# Tag.net
KiCad netlist of a schematic drawn in EasyEDA Pro
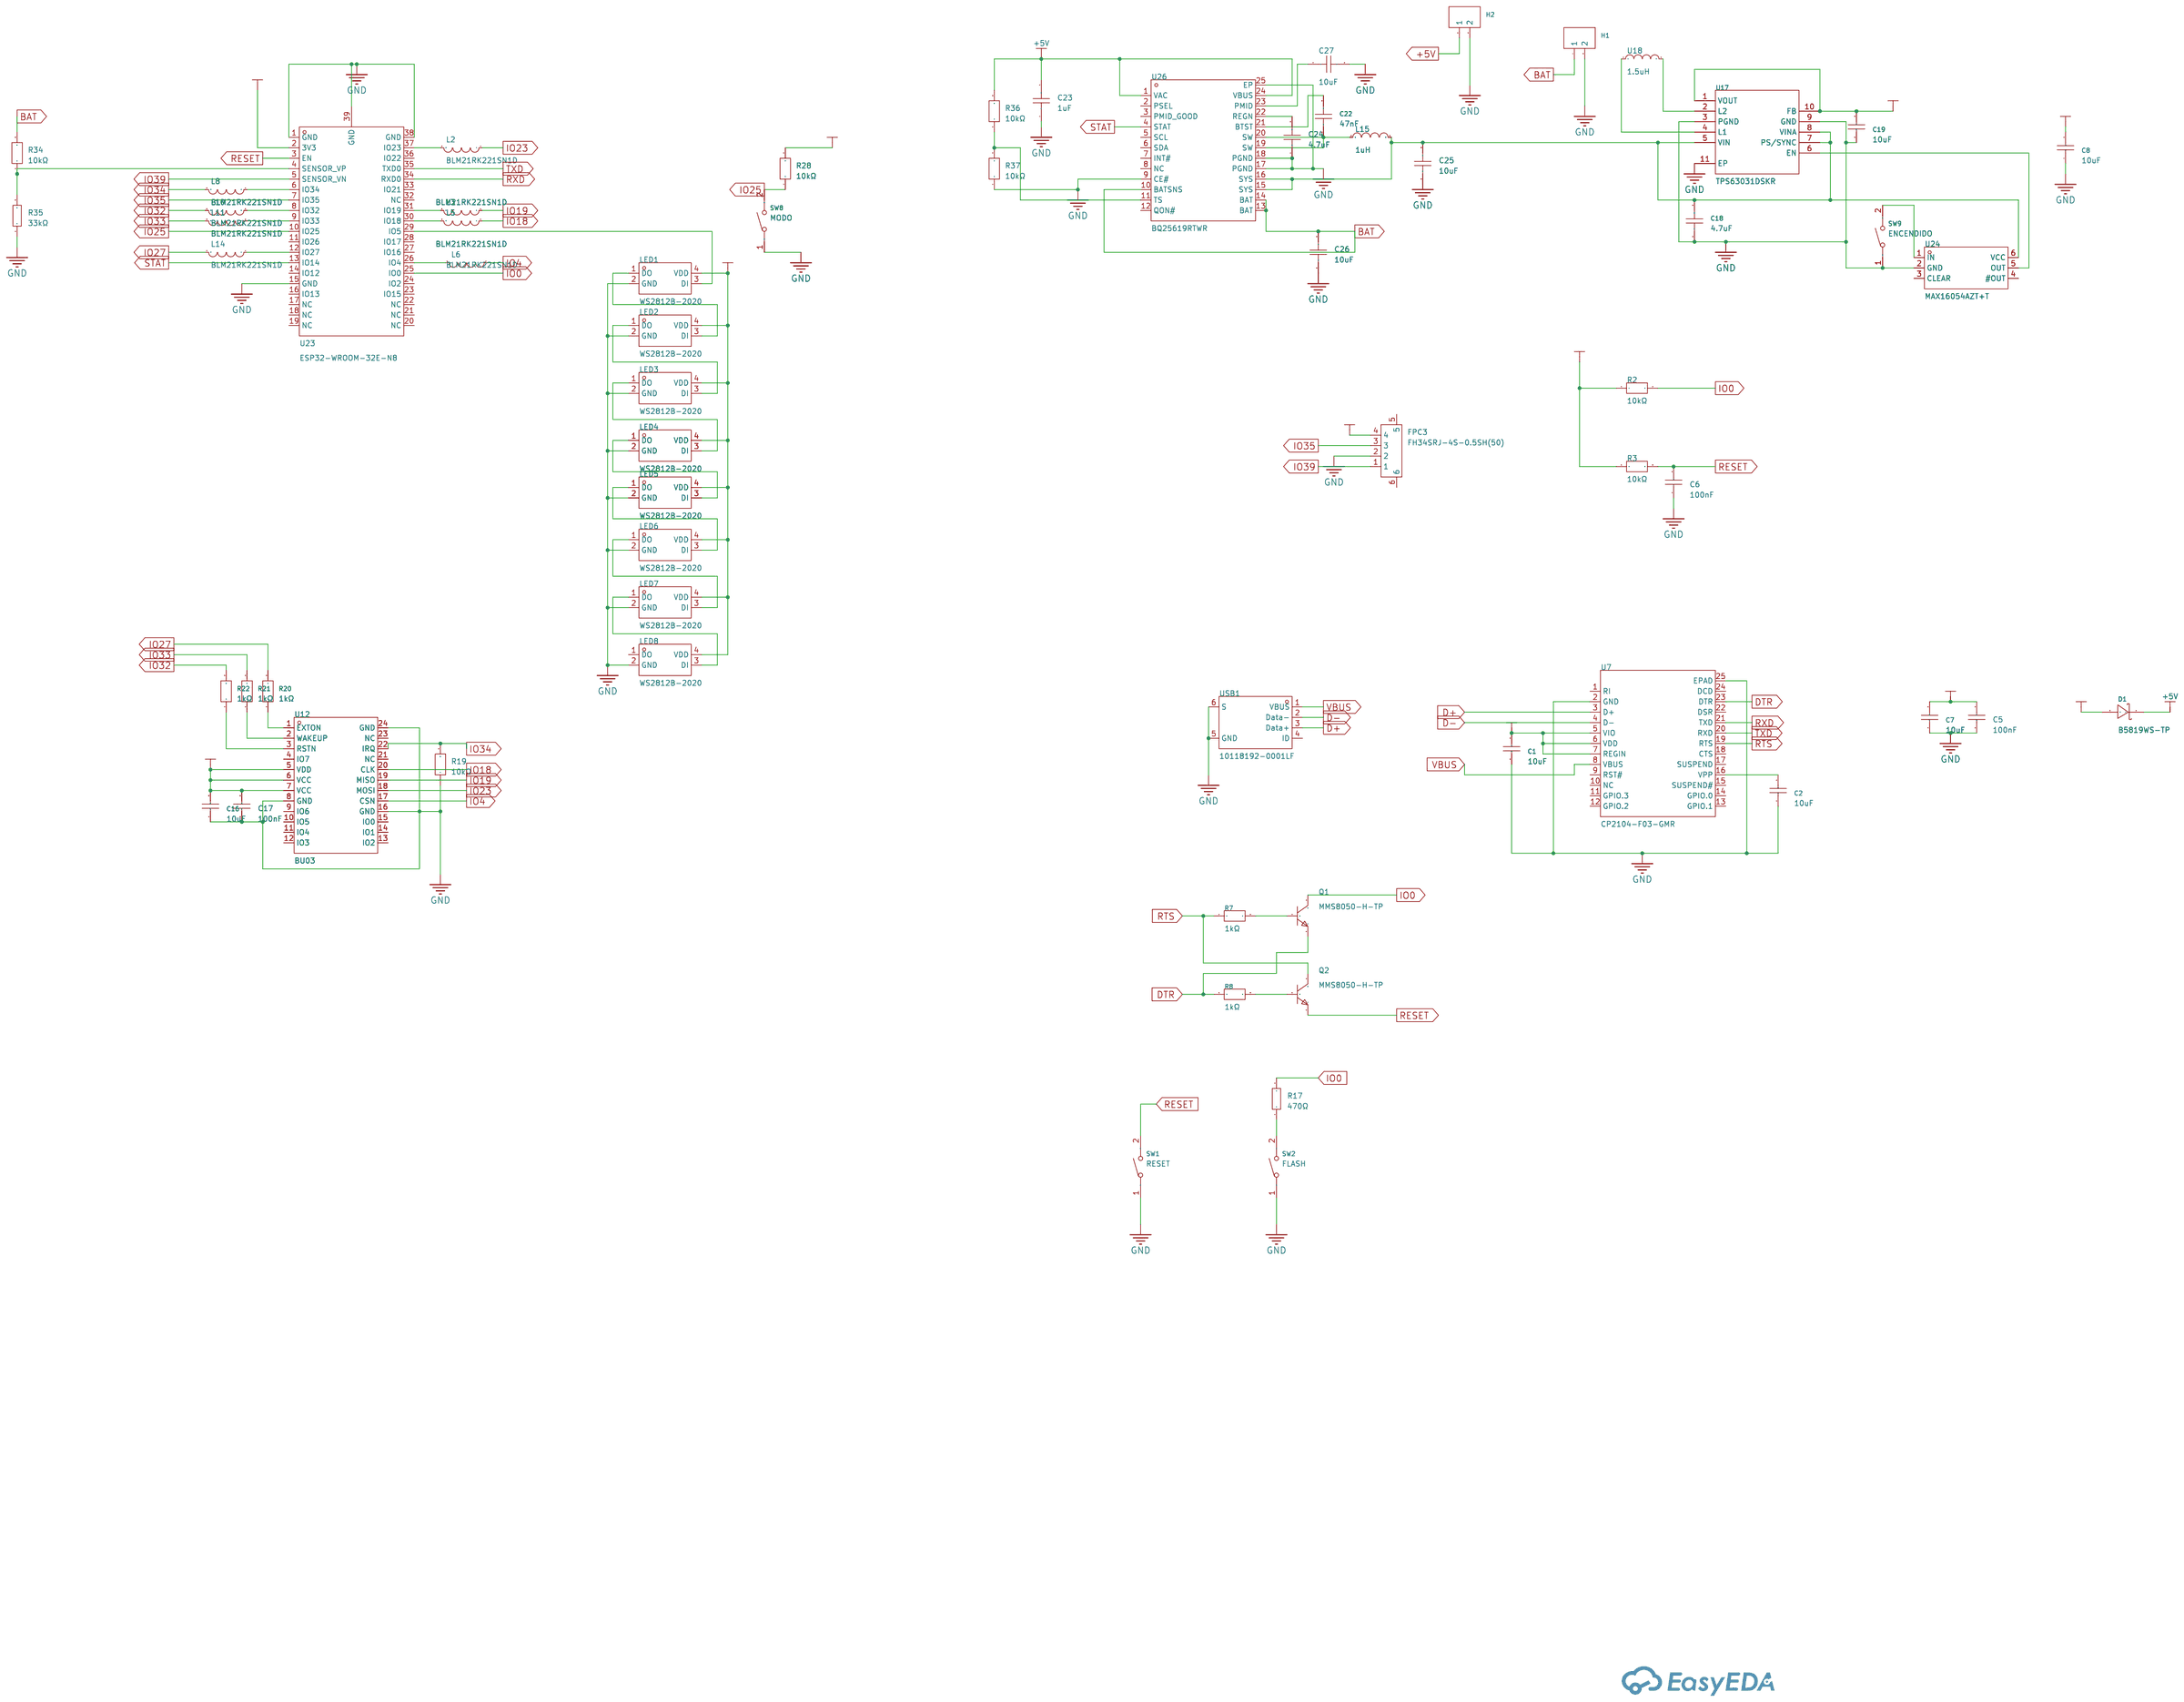
[diagram p0: schematic sheet]

(export (version "E")
  (design (tool "Eeschema 10.0.6"))
  (components
    (comp (ref "C1")
      (value "10uF")
      (footprint "easyedapro:C0805")
      (fields
        (field (name "Manufacturer Part") "CL21A106KPFNNNE")
        (field (name "Manufacturer") "SAMSUNG(三星)")
      )
      (libsource (lib "easyedapro") (part "CL21A106KPFNNNE"))
    )
    (comp (ref "C2")
      (value "10uF")
      (footprint "easyedapro:C0805")
      (fields
        (field (name "Manufacturer Part") "CL21A106KPFNNNE")
        (field (name "Manufacturer") "SAMSUNG(三星)")
      )
      (libsource (lib "easyedapro") (part "CL21A106KPFNNNE"))
    )
    (comp (ref "C5")
      (value "100nF")
      (footprint "easyedapro:C0805")
      (description "Capacitance:100nF Tolerance:±5% Tolerance:±5% Voltage Rating:50V Temperature Coefficient:X7R")
      (fields (field (name "Manufacturer Part") "0805B104J500NT") (field (name "Manufacturer") "FH(风华)"))
      (libsource (lib "easyedapro") (part "0805B104J500NT"))
    )
    (comp (ref "C6")
      (value "100nF")
      (footprint "easyedapro:C0805")
      (description "Capacitance:100nF Tolerance:±5% Tolerance:±5% Voltage Rating:50V Temperature Coefficient:X7R")
      (fields (field (name "Manufacturer Part") "0805B104J500NT") (field (name "Manufacturer") "FH(风华)"))
      (libsource (lib "easyedapro") (part "0805B104J500NT"))
    )
    (comp (ref "C7")
      (value "10uF")
      (footprint "easyedapro:C0805")
      (fields
        (field (name "Manufacturer Part") "CL21A106KPFNNNE")
        (field (name "Manufacturer") "SAMSUNG(三星)")
      )
      (libsource (lib "easyedapro") (part "CL21A106KPFNNNE"))
    )
    (comp (ref "C8")
      (value "10uF")
      (footprint "easyedapro:C0805")
      (fields
        (field (name "Manufacturer Part") "CL21A106KPFNNNE")
        (field (name "Manufacturer") "SAMSUNG(三星)")
      )
      (libsource (lib "easyedapro") (part "CL21A106KPFNNNE"))
    )
    (comp (ref "C16")
      (value "10uF")
      (footprint "easyedapro:C0805")
      (fields
        (field (name "Manufacturer Part") "CL21A106KPFNNNE")
        (field (name "Manufacturer") "SAMSUNG(三星)")
      )
      (libsource (lib "easyedapro") (part "CL21A106KPFNNNE"))
    )
    (comp (ref "C17")
      (value "100nF")
      (footprint "easyedapro:C0805")
      (description "Capacitance:100nF Tolerance:±5% Tolerance:±5% Voltage Rating:50V Temperature Coefficient:X7R")
      (fields (field (name "Manufacturer Part") "0805B104J500NT") (field (name "Manufacturer") "FH(风华)"))
      (libsource (lib "easyedapro") (part "0805B104J500NT"))
    )
    (comp (ref "C18")
      (value "4.7uF")
      (footprint "easyedapro:C0805")
      (fields
        (field (name "Manufacturer Part") "CC0805KKX7R5BB475")
        (field (name "Manufacturer") "YAGEO(国巨)")
      )
      (libsource (lib "easyedapro") (part "CC0805KKX7R5BB475"))
    )
    (comp (ref "C19")
      (value "10uF")
      (footprint "easyedapro:C0805")
      (fields
        (field (name "Manufacturer Part") "GCM21BR70J106KE22L")
        (field (name "Manufacturer") "muRata(村田)")
      )
      (libsource (lib "easyedapro") (part "GCM21BR70J106KE22L"))
    )
    (comp (ref "C22")
      (value "47nF")
      (footprint "easyedapro:C0805")
      (description "Capacitance:47nF Tolerance:±5% Tolerance:±5% Voltage Rating:50V Temperature Coefficient:X7R")
      (fields
        (field (name "Manufacturer Part") "CC0805JRX7R9BB473")
        (field (name "Manufacturer") "YAGEO(国巨)")
      )
      (libsource (lib "easyedapro") (part "CC0805JRX7R9BB473"))
    )
    (comp (ref "C23")
      (value "1uF")
      (footprint "easyedapro:C0805")
      (fields
        (field (name "Manufacturer Part") "CC0805JKX7R9BB105")
        (field (name "Manufacturer") "YAGEO(国巨)")
      )
      (libsource (lib "easyedapro") (part "CC0805JKX7R9BB105"))
    )
    (comp (ref "C24")
      (value "4.7uF")
      (footprint "easyedapro:C0805")
      (description "Capacitance:4.7uF Tolerance:±5% Tolerance:±5% Voltage Rating:6.3V Temperature Coefficient:X7R")
      (fields
        (field (name "Manufacturer Part") "C0805C475J9RACAUTO")
        (field (name "Manufacturer") "KEMET(基美)")
      )
      (libsource (lib "easyedapro") (part "C0805C475J9RACAUTO"))
    )
    (comp (ref "C25")
      (value "10uF")
      (footprint "easyedapro:C1206")
      (fields
        (field (name "Manufacturer Part") "C1206C106J3RACAUTO")
        (field (name "Manufacturer") "KEMET(基美)")
      )
      (libsource (lib "easyedapro") (part "C1206C106J3RACAUTO"))
    )
    (comp (ref "C26")
      (value "10uF")
      (footprint "easyedapro:C1206")
      (fields
        (field (name "Manufacturer Part") "C1206C106J3RACAUTO")
        (field (name "Manufacturer") "KEMET(基美)")
      )
      (libsource (lib "easyedapro") (part "C1206C106J3RACAUTO"))
    )
    (comp (ref "C27")
      (value "10uF")
      (footprint "easyedapro:C1206")
      (fields
        (field (name "Manufacturer Part") "C1206C106J3RACAUTO")
        (field (name "Manufacturer") "KEMET(基美)")
      )
      (libsource (lib "easyedapro") (part "C1206C106J3RACAUTO"))
    )
    (comp (ref "D1")
      (value "B5819WS-TP")
      (footprint "easyedapro:SOD-323_L1.8-W1.3-LS2.5-RD")
      (fields (field (name "Manufacturer") "MCC(美微科)"))
      (libsource (lib "easyedapro") (part "B5819WS-TP"))
    )
    (comp (ref "FPC3")
      (value "FH34SRJ-4S-0.5SH(50)")
      (footprint "easyedapro:FPC-SMD_FH34SRJ-4S-0.5SH-50")
      (fields (field (name "Manufacturer") "HRS(广濑)"))
      (libsource (lib "easyedapro") (part "FH34SRJ-4S-0.5SH(50)"))
    )
    (comp (ref "H1")
      (value "~")
      (footprint "easyedapro:HDR-TH_2P-P2.54-V-F")
      (libsource (lib "easyedapro") (part "Header-Female-2.54_1x2"))
    )
    (comp (ref "H2")
      (value "~")
      (footprint "easyedapro:HDR-TH_2P-P2.54-V-F")
      (libsource (lib "easyedapro") (part "Header-Female-2.54_1x2"))
    )
    (comp (ref "L2")
      (value "BLM21RK221SN1D")
      (footprint "easyedapro:L0805")
      (fields (field (name "Manufacturer") "muRata(村田)"))
      (libsource (lib "easyedapro") (part "BLM21RK221SN1D"))
    )
    (comp (ref "L3")
      (value "BLM21RK221SN1D")
      (footprint "easyedapro:L0805")
      (fields (field (name "Manufacturer") "muRata(村田)"))
      (libsource (lib "easyedapro") (part "BLM21RK221SN1D"))
    )
    (comp (ref "L5")
      (value "BLM21RK221SN1D")
      (footprint "easyedapro:L0805")
      (fields (field (name "Manufacturer") "muRata(村田)"))
      (libsource (lib "easyedapro") (part "BLM21RK221SN1D"))
    )
    (comp (ref "L6")
      (value "BLM21RK221SN1D")
      (footprint "easyedapro:L0805")
      (fields (field (name "Manufacturer") "muRata(村田)"))
      (libsource (lib "easyedapro") (part "BLM21RK221SN1D"))
    )
    (comp (ref "L8")
      (value "BLM21RK221SN1D")
      (footprint "easyedapro:L0805")
      (fields (field (name "Manufacturer") "muRata(村田)"))
      (libsource (lib "easyedapro") (part "BLM21RK221SN1D"))
    )
    (comp (ref "L10")
      (value "BLM21RK221SN1D")
      (footprint "easyedapro:L0805")
      (fields (field (name "Manufacturer") "muRata(村田)"))
      (libsource (lib "easyedapro") (part "BLM21RK221SN1D"))
    )
    (comp (ref "L11")
      (value "BLM21RK221SN1D")
      (footprint "easyedapro:L0805")
      (fields (field (name "Manufacturer") "muRata(村田)"))
      (libsource (lib "easyedapro") (part "BLM21RK221SN1D"))
    )
    (comp (ref "L14")
      (value "BLM21RK221SN1D")
      (footprint "easyedapro:L0805")
      (fields (field (name "Manufacturer") "muRata(村田)"))
      (libsource (lib "easyedapro") (part "BLM21RK221SN1D"))
    )
    (comp (ref "L15")
      (value "1uH")
      (footprint "easyedapro:IND-SMD_L5.4-W5.1")
      (description "Inductance:1uH Tolerance:±20% Tolerance:±20% Current Rating:5A DC Resistance(DCR):15mΩ")
      (fields
        (field (name "Manufacturer Part") "SLO0520H1R0MTT")
        (field (name "Manufacturer") "Sunltech(顺磁)")
      )
      (libsource (lib "easyedapro") (part "SLO0520H1R0MTT"))
    )
    (comp (ref "LED1")
      (value "WS2812B-2020")
      (footprint "easyedapro:LED-SMD_4P-L2.0-W2.0-TL_WS2812B-2020")
      (fields (field (name "Manufacturer") "worldsemi"))
      (libsource (lib "easyedapro") (part "WS2812B-2020"))
    )
    (comp (ref "LED2")
      (value "WS2812B-2020")
      (footprint "easyedapro:LED-SMD_4P-L2.0-W2.0-TL_WS2812B-2020")
      (fields (field (name "Manufacturer") "worldsemi"))
      (libsource (lib "easyedapro") (part "WS2812B-2020"))
    )
    (comp (ref "LED3")
      (value "WS2812B-2020")
      (footprint "easyedapro:LED-SMD_4P-L2.0-W2.0-TL_WS2812B-2020")
      (fields (field (name "Manufacturer") "worldsemi"))
      (libsource (lib "easyedapro") (part "WS2812B-2020"))
    )
    (comp (ref "LED4")
      (value "WS2812B-2020")
      (footprint "easyedapro:LED-SMD_4P-L2.0-W2.0-TL_WS2812B-2020")
      (fields (field (name "Manufacturer") "worldsemi"))
      (libsource (lib "easyedapro") (part "WS2812B-2020"))
    )
    (comp (ref "LED5")
      (value "WS2812B-2020")
      (footprint "easyedapro:LED-SMD_4P-L2.0-W2.0-TL_WS2812B-2020")
      (fields (field (name "Manufacturer") "worldsemi"))
      (libsource (lib "easyedapro") (part "WS2812B-2020"))
    )
    (comp (ref "LED6")
      (value "WS2812B-2020")
      (footprint "easyedapro:LED-SMD_4P-L2.0-W2.0-TL_WS2812B-2020")
      (fields (field (name "Manufacturer") "worldsemi"))
      (libsource (lib "easyedapro") (part "WS2812B-2020"))
    )
    (comp (ref "LED7")
      (value "WS2812B-2020")
      (footprint "easyedapro:LED-SMD_4P-L2.0-W2.0-TL_WS2812B-2020")
      (fields (field (name "Manufacturer") "worldsemi"))
      (libsource (lib "easyedapro") (part "WS2812B-2020"))
    )
    (comp (ref "LED8")
      (value "WS2812B-2020")
      (footprint "easyedapro:LED-SMD_4P-L2.0-W2.0-TL_WS2812B-2020")
      (fields (field (name "Manufacturer") "worldsemi"))
      (libsource (lib "easyedapro") (part "WS2812B-2020"))
    )
    (comp (ref "Q1")
      (value "MMS8050-H-TP")
      (footprint "easyedapro:SOT-23-3_L2.9-W1.3-P1.90-LS2.4-BR")
      (fields (field (name "Manufacturer") "MCC(美微科)"))
      (libsource (lib "easyedapro") (part "MMS8050-H-TP"))
    )
    (comp (ref "Q2")
      (value "MMS8050-H-TP")
      (footprint "easyedapro:SOT-23-3_L2.9-W1.3-P1.90-LS2.4-BR")
      (fields (field (name "Manufacturer") "MCC(美微科)"))
      (libsource (lib "easyedapro") (part "MMS8050-H-TP"))
    )
    (comp (ref "R2")
      (value "10kΩ")
      (footprint "easyedapro:R0805")
      (fields (field (name "Manufacturer Part") "ERJP06F1002V") (field (name "Manufacturer") "PANASONIC(松下)"))
      (libsource (lib "easyedapro") (part "ERJP06F1002V"))
    )
    (comp (ref "R3")
      (value "10kΩ")
      (footprint "easyedapro:R0805")
      (fields (field (name "Manufacturer Part") "ERJP06F1002V") (field (name "Manufacturer") "PANASONIC(松下)"))
      (libsource (lib "easyedapro") (part "ERJP06F1002V"))
    )
    (comp (ref "R7")
      (value "1kΩ")
      (footprint "easyedapro:R0805")
      (fields (field (name "Manufacturer Part") "ERJP06F1001V") (field (name "Manufacturer") "PANASONIC(松下)"))
      (libsource (lib "easyedapro") (part "ERJP06F1001V"))
    )
    (comp (ref "R8")
      (value "1kΩ")
      (footprint "easyedapro:R0805")
      (fields (field (name "Manufacturer Part") "ERJP06F1001V") (field (name "Manufacturer") "PANASONIC(松下)"))
      (libsource (lib "easyedapro") (part "ERJP06F1001V"))
    )
    (comp (ref "R17")
      (value "470Ω")
      (footprint "easyedapro:R0805")
      (fields (field (name "Manufacturer Part") "RC0805FR-07470RL") (field (name "Manufacturer") "YAGEO(国巨)"))
      (libsource (lib "easyedapro") (part "RC0805FR-07470RL"))
    )
    (comp (ref "R19")
      (value "10kΩ")
      (footprint "easyedapro:R0805")
      (fields (field (name "Manufacturer Part") "ERJP06F1002V") (field (name "Manufacturer") "PANASONIC(松下)"))
      (libsource (lib "easyedapro") (part "ERJP06F1002V"))
    )
    (comp (ref "R20")
      (value "1kΩ")
      (footprint "easyedapro:R0805")
      (fields (field (name "Manufacturer Part") "ERJP06F1001V") (field (name "Manufacturer") "PANASONIC(松下)"))
      (libsource (lib "easyedapro") (part "ERJP06F1001V"))
    )
    (comp (ref "R21")
      (value "1kΩ")
      (footprint "easyedapro:R0805")
      (fields (field (name "Manufacturer Part") "ERJP06F1001V") (field (name "Manufacturer") "PANASONIC(松下)"))
      (libsource (lib "easyedapro") (part "ERJP06F1001V"))
    )
    (comp (ref "R22")
      (value "1kΩ")
      (footprint "easyedapro:R0805")
      (fields (field (name "Manufacturer Part") "ERJP06F1001V") (field (name "Manufacturer") "PANASONIC(松下)"))
      (libsource (lib "easyedapro") (part "ERJP06F1001V"))
    )
    (comp (ref "R28")
      (value "10kΩ")
      (footprint "easyedapro:R0805")
      (fields (field (name "Manufacturer Part") "ERJP06F1002V") (field (name "Manufacturer") "PANASONIC(松下)"))
      (libsource (lib "easyedapro") (part "ERJP06F1002V"))
    )
    (comp (ref "R34")
      (value "10kΩ")
      (footprint "easyedapro:R0805")
      (fields (field (name "Manufacturer Part") "ERJP06F1002V") (field (name "Manufacturer") "PANASONIC(松下)"))
      (libsource (lib "easyedapro") (part "ERJP06F1002V"))
    )
    (comp (ref "R35")
      (value "33kΩ")
      (footprint "easyedapro:R0805")
      (fields (field (name "Manufacturer Part") "RC0805FR-0733KL") (field (name "Manufacturer") "YAGEO(国巨)"))
      (libsource (lib "easyedapro") (part "RC0805FR-0733KL"))
    )
    (comp (ref "R36")
      (value "10kΩ")
      (footprint "easyedapro:R0805")
      (fields (field (name "Manufacturer Part") "ERJP06F1002V") (field (name "Manufacturer") "PANASONIC(松下)"))
      (libsource (lib "easyedapro") (part "ERJP06F1002V"))
    )
    (comp (ref "R37")
      (value "10kΩ")
      (footprint "easyedapro:R0805")
      (fields (field (name "Manufacturer Part") "ERJP06F1002V") (field (name "Manufacturer") "PANASONIC(松下)"))
      (libsource (lib "easyedapro") (part "ERJP06F1002V"))
    )
    (comp (ref "SW1")
      (value "RESET")
      (footprint "easyedapro:SW-SMD_L3.9-W3.0-P4.45")
      (fields (field (name "Manufacturer Part") "TS-1088-AR02016") (field (name "Manufacturer") "XUNPU(讯普)"))
      (libsource (lib "easyedapro") (part "TS-1088-AR02016"))
    )
    (comp (ref "SW2")
      (value "FLASH")
      (footprint "easyedapro:SW-SMD_L3.9-W3.0-P4.45")
      (fields (field (name "Manufacturer Part") "TS-1088-AR02016") (field (name "Manufacturer") "XUNPU(讯普)"))
      (libsource (lib "easyedapro") (part "TS-1088-AR02016"))
    )
    (comp (ref "SW8")
      (value "MODO")
      (footprint "easyedapro:SW-SMD_L3.9-W3.0-P4.45")
      (fields (field (name "Manufacturer Part") "TS-1088-AR02016") (field (name "Manufacturer") "XUNPU(讯普)"))
      (libsource (lib "easyedapro") (part "TS-1088-AR02016"))
    )
    (comp (ref "SW9")
      (value "ENCENDIDO")
      (footprint "easyedapro:SW-SMD_L3.9-W3.0-P4.45")
      (fields (field (name "Manufacturer Part") "TS-1088-AR02016") (field (name "Manufacturer") "XUNPU(讯普)"))
      (libsource (lib "easyedapro") (part "TS-1088-AR02016"))
    )
    (comp (ref "U7")
      (value "CP2104-F03-GMR")
      (footprint "easyedapro:QFN-24_L4.0-W4.0-P0.50-BL-EP2.7")
      (fields (field (name "Manufacturer") "SKYWORKS/SILICON LABS(芯科)"))
      (libsource (lib "easyedapro") (part "CP2104-F03-GM"))
    )
    (comp (ref "U12")
      (value "BU03")
      (footprint "easyedapro:WIRELM-SMD_BU03")
      (fields (field (name "Manufacturer") "Ai-Thinker(安信可)"))
      (libsource (lib "easyedapro") (part "BU03"))
    )
    (comp (ref "U17")
      (value "TPS63031DSKR")
      (footprint "easyedapro:SON-10_L2.5-W2.5-P0.50-TL-EP")
      (fields (field (name "Manufacturer") "TI(德州仪器)"))
      (libsource (lib "easyedapro") (part "TPS63031DSKR"))
    )
    (comp (ref "U18")
      (value "1.5uH")
      (footprint "easyedapro:IND-SMD_L2.5-W2.0_MHCHL2520")
      (fields (field (name "Manufacturer Part") "SPM2512-1R5M") (field (name "Manufacturer") "KOHERelec(科或)"))
      (libsource (lib "easyedapro") (part "SPM2512-1R5M"))
    )
    (comp (ref "U23")
      (value "ESP32-WROOM-32E-N8")
      (footprint "easyedapro:WIFI-SMD_ESP32-WROOM-32E")
      (fields (field (name "Manufacturer") "ESPRESSIF(乐鑫)"))
      (libsource (lib "easyedapro") (part "ESP32-WROOM-32E(8MB)"))
    )
    (comp (ref "U24")
      (value "MAX16054AZT+T")
      (footprint "easyedapro:TSOT-23-6_L2.9-W1.6-P0.95-LS2.8-TL")
      (fields (field (name "Manufacturer") "ADI(亚德诺)"))
      (libsource (lib "easyedapro") (part "MAX16054AZT+T"))
    )
    (comp (ref "U26")
      (value "BQ25619RTWR")
      (footprint "easyedapro:WQFN-24_L4.0-W4.0-P0.50-TL-EP2.7")
      (fields (field (name "Manufacturer") "TI(德州仪器)"))
      (libsource (lib "easyedapro") (part "BQ25619RTWR"))
    )
    (comp (ref "USB1")
      (value "10118192-0001LF")
      (footprint "easyedapro:MICRO-USB-SMD_10118192-0001LF_1")
      (fields (field (name "Manufacturer") "Amphenol"))
      (libsource (lib "easyedapro") (part "10118192-0001LF"))
    )
  )
  (nets
    (net (code "1") (name "+3V3") (class "Default")
      (node (ref "C1") (pin "2") (pinfunction "2_2") (pintype "input"))
      (node (ref "C16") (pin "2") (pinfunction "2_2") (pintype "input"))
      (node (ref "C17") (pin "2") (pinfunction "2_2") (pintype "input"))
      (node (ref "C19") (pin "2") (pinfunction "2_2") (pintype "input"))
      (node (ref "C8") (pin "2") (pinfunction "2_2") (pintype "input"))
      (node (ref "FPC3") (pin "4") (pinfunction "4_4") (pintype "unspecified"))
      (node (ref "LED1") (pin "4") (pinfunction "VDD_4") (pintype "unspecified"))
      (node (ref "LED2") (pin "4") (pinfunction "VDD_4") (pintype "unspecified"))
      (node (ref "LED3") (pin "4") (pinfunction "VDD_4") (pintype "unspecified"))
      (node (ref "LED4") (pin "4") (pinfunction "VDD_4") (pintype "unspecified"))
      (node (ref "LED5") (pin "4") (pinfunction "VDD_4") (pintype "unspecified"))
      (node (ref "LED6") (pin "4") (pinfunction "VDD_4") (pintype "unspecified"))
      (node (ref "LED7") (pin "4") (pinfunction "VDD_4") (pintype "unspecified"))
      (node (ref "LED8") (pin "4") (pinfunction "VDD_4") (pintype "unspecified"))
      (node (ref "R2") (pin "1") (pinfunction "1_1") (pintype "unspecified"))
      (node (ref "R28") (pin "2") (pinfunction "2_2") (pintype "unspecified"))
      (node (ref "R3") (pin "1") (pinfunction "1_1") (pintype "unspecified"))
      (node (ref "U12") (pin "5") (pinfunction "VDD_5") (pintype "unspecified"))
      (node (ref "U12") (pin "6") (pinfunction "VCC_6") (pintype "unspecified"))
      (node (ref "U12") (pin "7") (pinfunction "VCC_7") (pintype "unspecified"))
      (node (ref "U17") (pin "1") (pinfunction "VOUT_1") (pintype "input"))
      (node (ref "U17") (pin "10") (pinfunction "FB_10") (pintype "input"))
      (node (ref "U23") (pin "2") (pinfunction "3V3_2") (pintype "unspecified"))
      (node (ref "U7") (pin "5") (pinfunction "VIO_5") (pintype "unspecified"))
      (node (ref "U7") (pin "6") (pinfunction "VDD_6") (pintype "unspecified"))
      (node (ref "U7") (pin "7") (pinfunction "REGIN_7") (pintype "unspecified"))
    )
    (net (code "2") (name "+5V") (class "Default")
      (node (ref "C23") (pin "2") (pinfunction "2_2") (pintype "unspecified"))
      (node (ref "D1") (pin "1") (pinfunction "K_1") (pintype "input"))
      (node (ref "H2") (pin "1") (pinfunction "1_1") (pintype "input"))
      (node (ref "R36") (pin "2") (pinfunction "2_2") (pintype "unspecified"))
      (node (ref "U26") (pin "1") (pinfunction "VAC_1") (pintype "unspecified"))
      (node (ref "U26") (pin "24") (pinfunction "VBUS_24") (pintype "unspecified"))
    )
    (net (code "3") (name "BAT") (class "Default")
      (node (ref "C26") (pin "2") (pinfunction "2_2") (pintype "unspecified"))
      (node (ref "H1") (pin "1") (pinfunction "1_1") (pintype "input"))
      (node (ref "R34") (pin "2") (pinfunction "2_2") (pintype "unspecified"))
      (node (ref "U26") (pin "10") (pinfunction "BATSNS_10") (pintype "unspecified"))
      (node (ref "U26") (pin "13") (pinfunction "BAT_13") (pintype "unspecified"))
      (node (ref "U26") (pin "14") (pinfunction "BAT_14") (pintype "unspecified"))
    )
    (net (code "4") (name "D+") (class "Default")
      (node (ref "U7") (pin "3") (pinfunction "D+_3") (pintype "unspecified"))
      (node (ref "USB1") (pin "3") (pinfunction "Data+_3") (pintype "unspecified"))
    )
    (net (code "5") (name "D-") (class "Default")
      (node (ref "U7") (pin "4") (pinfunction "D-_4") (pintype "unspecified"))
      (node (ref "USB1") (pin "2") (pinfunction "Data-_2") (pintype "unspecified"))
    )
    (net (code "6") (name "DTR") (class "Default")
      (node (ref "Q1") (pin "2") (pinfunction "E_2") (pintype "input"))
      (node (ref "R8") (pin "1") (pinfunction "1_1") (pintype "input"))
      (node (ref "U7") (pin "23") (pinfunction "DTR_23") (pintype "unspecified"))
    )
    (net (code "7") (name "GND") (class "Default")
      (node (ref "C1") (pin "1") (pinfunction "1_1") (pintype "input"))
      (node (ref "C16") (pin "1") (pinfunction "1_1") (pintype "input"))
      (node (ref "C17") (pin "1") (pinfunction "1_1") (pintype "input"))
      (node (ref "C18") (pin "1") (pinfunction "1_1") (pintype "input"))
      (node (ref "C19") (pin "1") (pinfunction "1_1") (pintype "input"))
      (node (ref "C2") (pin "1") (pinfunction "1_1") (pintype "input"))
      (node (ref "C23") (pin "1") (pinfunction "1_1") (pintype "unspecified"))
      (node (ref "C24") (pin "1") (pinfunction "1_1") (pintype "unspecified"))
      (node (ref "C25") (pin "1") (pinfunction "1_1") (pintype "unspecified"))
      (node (ref "C26") (pin "1") (pinfunction "1_1") (pintype "unspecified"))
      (node (ref "C27") (pin "2") (pinfunction "2_2") (pintype "unspecified"))
      (node (ref "C5") (pin "1") (pinfunction "1_1") (pintype "input"))
      (node (ref "C6") (pin "1") (pinfunction "1_1") (pintype "input"))
      (node (ref "C7") (pin "1") (pinfunction "1_1") (pintype "input"))
      (node (ref "C8") (pin "1") (pinfunction "1_1") (pintype "input"))
      (node (ref "FPC3") (pin "2") (pinfunction "2_2") (pintype "unspecified"))
      (node (ref "H1") (pin "2") (pinfunction "2_2") (pintype "input"))
      (node (ref "H2") (pin "2") (pinfunction "2_2") (pintype "input"))
      (node (ref "LED1") (pin "2") (pinfunction "GND_2") (pintype "unspecified"))
      (node (ref "LED2") (pin "2") (pinfunction "GND_2") (pintype "unspecified"))
      (node (ref "LED3") (pin "2") (pinfunction "GND_2") (pintype "unspecified"))
      (node (ref "LED4") (pin "2") (pinfunction "GND_2") (pintype "unspecified"))
      (node (ref "LED5") (pin "2") (pinfunction "GND_2") (pintype "unspecified"))
      (node (ref "LED6") (pin "2") (pinfunction "GND_2") (pintype "unspecified"))
      (node (ref "LED7") (pin "2") (pinfunction "GND_2") (pintype "unspecified"))
      (node (ref "LED8") (pin "2") (pinfunction "GND_2") (pintype "unspecified"))
      (node (ref "R19") (pin "1") (pinfunction "1_1") (pintype "unspecified"))
      (node (ref "R35") (pin "1") (pinfunction "1_1") (pintype "input"))
      (node (ref "R37") (pin "1") (pinfunction "1_1") (pintype "unspecified"))
      (node (ref "SW1") (pin "1") (pinfunction "1_1") (pintype "input"))
      (node (ref "SW2") (pin "1") (pinfunction "1_1") (pintype "input"))
      (node (ref "SW8") (pin "1") (pinfunction "1_1") (pintype "input"))
      (node (ref "SW9") (pin "1") (pinfunction "1_1") (pintype "input"))
      (node (ref "U12") (pin "16") (pinfunction "GND_16") (pintype "unspecified"))
      (node (ref "U12") (pin "24") (pinfunction "GND_24") (pintype "unspecified"))
      (node (ref "U12") (pin "8") (pinfunction "GND_8") (pintype "unspecified"))
      (node (ref "U17") (pin "11") (pinfunction "EP_11") (pintype "input"))
      (node (ref "U17") (pin "3") (pinfunction "PGND_3") (pintype "input"))
      (node (ref "U17") (pin "9") (pinfunction "GND_9") (pintype "input"))
      (node (ref "U23") (pin "1") (pinfunction "GND_1") (pintype "unspecified"))
      (node (ref "U23") (pin "15") (pinfunction "GND_15") (pintype "unspecified"))
      (node (ref "U23") (pin "38") (pinfunction "GND_38") (pintype "unspecified"))
      (node (ref "U23") (pin "39") (pinfunction "GND_39") (pintype "unspecified"))
      (node (ref "U24") (pin "2") (pinfunction "GND_2") (pintype "unspecified"))
      (node (ref "U26") (pin "17") (pinfunction "PGND_17") (pintype "unspecified"))
      (node (ref "U26") (pin "18") (pinfunction "PGND_18") (pintype "unspecified"))
      (node (ref "U26") (pin "25") (pinfunction "EP_25") (pintype "unspecified"))
      (node (ref "U26") (pin "9") (pinfunction "CE#_9") (pintype "unspecified"))
      (node (ref "U7") (pin "2") (pinfunction "GND_2") (pintype "unspecified"))
      (node (ref "U7") (pin "25") (pinfunction "EPAD_25") (pintype "unspecified"))
      (node (ref "USB1") (pin "5") (pinfunction "GND_5") (pintype "unspecified"))
      (node (ref "USB1") (pin "6") (pinfunction "S_6") (pintype "unspecified"))
    )
    (net (code "8") (name "IO0") (class "Default")
      (node (ref "Q1") (pin "3") (pinfunction "C_3") (pintype "input"))
      (node (ref "R17") (pin "2") (pinfunction "2_2") (pintype "input"))
      (node (ref "R2") (pin "2") (pinfunction "2_2") (pintype "unspecified"))
      (node (ref "U23") (pin "25") (pinfunction "IO0_25") (pintype "unspecified"))
    )
    (net (code "9") (name "IO4") (class "Default")
      (node (ref "L6") (pin "1") (pinfunction "1_1") (pintype "unspecified"))
      (node (ref "U12") (pin "17") (pinfunction "CSN_17") (pintype "unspecified"))
    )
    (net (code "10") (name "IO18") (class "Default")
      (node (ref "L5") (pin "1") (pinfunction "1_1") (pintype "unspecified"))
      (node (ref "U12") (pin "20") (pinfunction "CLK_20") (pintype "unspecified"))
    )
    (net (code "11") (name "IO19") (class "Default")
      (node (ref "L3") (pin "1") (pinfunction "1_1") (pintype "unspecified"))
      (node (ref "U12") (pin "19") (pinfunction "MISO_19") (pintype "unspecified"))
    )
    (net (code "12") (name "IO23") (class "Default")
      (node (ref "L2") (pin "1") (pinfunction "1_1") (pintype "unspecified"))
      (node (ref "U12") (pin "18") (pinfunction "MOSI_18") (pintype "unspecified"))
    )
    (net (code "13") (name "IO25") (class "Default")
      (node (ref "R28") (pin "1") (pinfunction "1_1") (pintype "unspecified"))
      (node (ref "SW8") (pin "2") (pinfunction "2_2") (pintype "input"))
      (node (ref "U23") (pin "10") (pinfunction "IO25_10") (pintype "unspecified"))
    )
    (net (code "14") (name "IO27") (class "Default")
      (node (ref "L14") (pin "2") (pinfunction "2_2") (pintype "unspecified"))
      (node (ref "R20") (pin "2") (pinfunction "2_2") (pintype "input"))
    )
    (net (code "15") (name "IO32") (class "Default")
      (node (ref "L10") (pin "2") (pinfunction "2_2") (pintype "unspecified"))
      (node (ref "R22") (pin "2") (pinfunction "2_2") (pintype "input"))
    )
    (net (code "16") (name "IO33") (class "Default")
      (node (ref "L11") (pin "2") (pinfunction "2_2") (pintype "unspecified"))
      (node (ref "R21") (pin "2") (pinfunction "2_2") (pintype "input"))
    )
    (net (code "17") (name "IO34") (class "Default")
      (node (ref "L8") (pin "2") (pinfunction "2_2") (pintype "unspecified"))
      (node (ref "R19") (pin "2") (pinfunction "2_2") (pintype "unspecified"))
      (node (ref "U12") (pin "22") (pinfunction "IRQ_22") (pintype "unspecified"))
    )
    (net (code "18") (name "IO35") (class "Default")
      (node (ref "FPC3") (pin "3") (pinfunction "3_3") (pintype "unspecified"))
      (node (ref "U23") (pin "7") (pinfunction "IO35_7") (pintype "unspecified"))
    )
    (net (code "19") (name "IO39") (class "Default")
      (node (ref "FPC3") (pin "1") (pinfunction "1_1") (pintype "unspecified"))
      (node (ref "U23") (pin "5") (pinfunction "SENSOR_VN_5") (pintype "unspecified"))
    )
    (net (code "20") (name "Net-(C22-Pad1)") (class "Default")
      (node (ref "C22") (pin "1") (pinfunction "1_1") (pintype "input"))
      (node (ref "L15") (pin "1") (pinfunction "1_1") (pintype "unspecified"))
      (node (ref "U26") (pin "19") (pinfunction "SW_19") (pintype "unspecified"))
      (node (ref "U26") (pin "20") (pinfunction "SW_20") (pintype "unspecified"))
    )
    (net (code "21") (name "Net-(LED1-DI)") (class "Default")
      (node (ref "LED1") (pin "3") (pinfunction "DI_3") (pintype "unspecified"))
      (node (ref "U23") (pin "29") (pinfunction "IO5_29") (pintype "unspecified"))
    )
    (net (code "22") (name "Net-(LED1-DO)") (class "Default")
      (node (ref "LED1") (pin "1") (pinfunction "DO_1") (pintype "unspecified"))
      (node (ref "LED2") (pin "3") (pinfunction "DI_3") (pintype "unspecified"))
    )
    (net (code "23") (name "Net-(LED2-DO)") (class "Default")
      (node (ref "LED2") (pin "1") (pinfunction "DO_1") (pintype "unspecified"))
      (node (ref "LED3") (pin "3") (pinfunction "DI_3") (pintype "unspecified"))
    )
    (net (code "24") (name "Net-(LED3-DO)") (class "Default")
      (node (ref "LED3") (pin "1") (pinfunction "DO_1") (pintype "unspecified"))
      (node (ref "LED4") (pin "3") (pinfunction "DI_3") (pintype "unspecified"))
    )
    (net (code "25") (name "Net-(LED4-DO)") (class "Default")
      (node (ref "LED4") (pin "1") (pinfunction "DO_1") (pintype "unspecified"))
      (node (ref "LED5") (pin "3") (pinfunction "DI_3") (pintype "unspecified"))
    )
    (net (code "26") (name "Net-(LED5-DO)") (class "Default")
      (node (ref "LED5") (pin "1") (pinfunction "DO_1") (pintype "unspecified"))
      (node (ref "LED6") (pin "3") (pinfunction "DI_3") (pintype "unspecified"))
    )
    (net (code "27") (name "Net-(LED6-DO)") (class "Default")
      (node (ref "LED6") (pin "1") (pinfunction "DO_1") (pintype "unspecified"))
      (node (ref "LED7") (pin "3") (pinfunction "DI_3") (pintype "unspecified"))
    )
    (net (code "28") (name "Net-(LED7-DO)") (class "Default")
      (node (ref "LED7") (pin "1") (pinfunction "DO_1") (pintype "unspecified"))
      (node (ref "LED8") (pin "3") (pinfunction "DI_3") (pintype "unspecified"))
    )
    (net (code "29") (name "Net-(Q1-B)") (class "Default")
      (node (ref "Q1") (pin "1") (pinfunction "B_1") (pintype "input"))
      (node (ref "R7") (pin "2") (pinfunction "2_2") (pintype "input"))
    )
    (net (code "30") (name "Net-(Q2-B)") (class "Default")
      (node (ref "Q2") (pin "1") (pinfunction "B_1") (pintype "input"))
      (node (ref "R8") (pin "2") (pinfunction "2_2") (pintype "input"))
    )
    (net (code "31") (name "Net-(R17-Pad1)") (class "Default")
      (node (ref "R17") (pin "1") (pinfunction "1_1") (pintype "input"))
      (node (ref "SW2") (pin "2") (pinfunction "2_2") (pintype "input"))
    )
    (net (code "32") (name "Net-(U7-VPP)") (class "Default")
      (node (ref "C2") (pin "2") (pinfunction "2_2") (pintype "input"))
      (node (ref "U7") (pin "16") (pinfunction "VPP_16") (pintype "unspecified"))
    )
    (net (code "33") (name "Net-(U12-EXTON)") (class "Default")
      (node (ref "R20") (pin "1") (pinfunction "1_1") (pintype "input"))
      (node (ref "U12") (pin "1") (pinfunction "EXTON_1") (pintype "unspecified"))
    )
    (net (code "34") (name "Net-(U12-RSTN)") (class "Default")
      (node (ref "R22") (pin "1") (pinfunction "1_1") (pintype "input"))
      (node (ref "U12") (pin "3") (pinfunction "RSTN_3") (pintype "unspecified"))
    )
    (net (code "35") (name "Net-(U12-WAKEUP)") (class "Default")
      (node (ref "R21") (pin "1") (pinfunction "1_1") (pintype "input"))
      (node (ref "U12") (pin "2") (pinfunction "WAKEUP_2") (pintype "unspecified"))
    )
    (net (code "36") (name "Net-(U17-EN)") (class "Default")
      (node (ref "U17") (pin "6") (pinfunction "EN_6") (pintype "input"))
      (node (ref "U24") (pin "5") (pinfunction "OUT_5") (pintype "unspecified"))
    )
    (net (code "37") (name "Net-(U17-L1)") (class "Default")
      (node (ref "U17") (pin "4") (pinfunction "L1_4") (pintype "input"))
      (node (ref "U18") (pin "1") (pinfunction "1_1") (pintype "unspecified"))
    )
    (net (code "38") (name "Net-(U17-L2)") (class "Default")
      (node (ref "U17") (pin "2") (pinfunction "L2_2") (pintype "input"))
      (node (ref "U18") (pin "2") (pinfunction "2_2") (pintype "unspecified"))
    )
    (net (code "39") (name "Net-(U17-PS{slash}SYNC)") (class "Default")
      (node (ref "C18") (pin "2") (pinfunction "2_2") (pintype "input"))
      (node (ref "C25") (pin "2") (pinfunction "2_2") (pintype "unspecified"))
      (node (ref "L15") (pin "2") (pinfunction "2_2") (pintype "unspecified"))
      (node (ref "U17") (pin "5") (pinfunction "VIN_5") (pintype "input"))
      (node (ref "U17") (pin "7") (pinfunction "PS/SYNC_7") (pintype "input"))
      (node (ref "U17") (pin "8") (pinfunction "VINA_8") (pintype "input"))
      (node (ref "U24") (pin "6") (pinfunction "VCC_6") (pintype "unspecified"))
      (node (ref "U26") (pin "15") (pinfunction "SYS_15") (pintype "unspecified"))
      (node (ref "U26") (pin "16") (pinfunction "SYS_16") (pintype "unspecified"))
    )
    (net (code "40") (name "Net-(U23-IO4)") (class "Default")
      (node (ref "L6") (pin "2") (pinfunction "2_2") (pintype "unspecified"))
      (node (ref "U23") (pin "26") (pinfunction "IO4_26") (pintype "unspecified"))
    )
    (net (code "41") (name "Net-(U23-IO18)") (class "Default")
      (node (ref "L5") (pin "2") (pinfunction "2_2") (pintype "unspecified"))
      (node (ref "U23") (pin "30") (pinfunction "IO18_30") (pintype "unspecified"))
    )
    (net (code "42") (name "Net-(U23-IO19)") (class "Default")
      (node (ref "L3") (pin "2") (pinfunction "2_2") (pintype "unspecified"))
      (node (ref "U23") (pin "31") (pinfunction "IO19_31") (pintype "unspecified"))
    )
    (net (code "43") (name "Net-(U23-IO23)") (class "Default")
      (node (ref "L2") (pin "2") (pinfunction "2_2") (pintype "unspecified"))
      (node (ref "U23") (pin "37") (pinfunction "IO23_37") (pintype "unspecified"))
    )
    (net (code "44") (name "Net-(U23-IO27)") (class "Default")
      (node (ref "L14") (pin "1") (pinfunction "1_1") (pintype "unspecified"))
      (node (ref "U23") (pin "12") (pinfunction "IO27_12") (pintype "unspecified"))
    )
    (net (code "45") (name "Net-(U23-IO32)") (class "Default")
      (node (ref "L10") (pin "1") (pinfunction "1_1") (pintype "unspecified"))
      (node (ref "U23") (pin "8") (pinfunction "IO32_8") (pintype "unspecified"))
    )
    (net (code "46") (name "Net-(U23-IO33)") (class "Default")
      (node (ref "L11") (pin "1") (pinfunction "1_1") (pintype "unspecified"))
      (node (ref "U23") (pin "9") (pinfunction "IO33_9") (pintype "unspecified"))
    )
    (net (code "47") (name "Net-(U23-IO34)") (class "Default")
      (node (ref "L8") (pin "1") (pinfunction "1_1") (pintype "unspecified"))
      (node (ref "U23") (pin "6") (pinfunction "IO34_6") (pintype "unspecified"))
    )
    (net (code "48") (name "Net-(U23-SENSOR_VP)") (class "Default")
      (node (ref "R34") (pin "1") (pinfunction "1_1") (pintype "unspecified"))
      (node (ref "R35") (pin "2") (pinfunction "2_2") (pintype "input"))
      (node (ref "U23") (pin "4") (pinfunction "SENSOR_VP_4") (pintype "unspecified"))
    )
    (net (code "49") (name "Net-(U24-IN)") (class "Default")
      (node (ref "SW9") (pin "2") (pinfunction "2_2") (pintype "input"))
      (node (ref "U24") (pin "1") (pinfunction "IN_1") (pintype "unspecified"))
    )
    (net (code "50") (name "Net-(U26-BTST)") (class "Default")
      (node (ref "C22") (pin "2") (pinfunction "2_2") (pintype "input"))
      (node (ref "U26") (pin "21") (pinfunction "BTST_21") (pintype "unspecified"))
    )
    (net (code "51") (name "Net-(U26-PMID)") (class "Default")
      (node (ref "C27") (pin "1") (pinfunction "1_1") (pintype "unspecified"))
      (node (ref "U26") (pin "23") (pinfunction "PMID_23") (pintype "unspecified"))
    )
    (net (code "52") (name "Net-(U26-REGN)") (class "Default")
      (node (ref "C24") (pin "2") (pinfunction "2_2") (pintype "unspecified"))
      (node (ref "U26") (pin "22") (pinfunction "REGN_22") (pintype "unspecified"))
    )
    (net (code "53") (name "Net-(U26-TS)") (class "Default")
      (node (ref "R36") (pin "1") (pinfunction "1_1") (pintype "unspecified"))
      (node (ref "R37") (pin "2") (pinfunction "2_2") (pintype "unspecified"))
      (node (ref "U26") (pin "11") (pinfunction "TS_11") (pintype "unspecified"))
    )
    (net (code "54") (name "RESET") (class "Default")
      (node (ref "C6") (pin "2") (pinfunction "2_2") (pintype "input"))
      (node (ref "Q2") (pin "2") (pinfunction "E_2") (pintype "input"))
      (node (ref "R3") (pin "2") (pinfunction "2_2") (pintype "unspecified"))
      (node (ref "SW1") (pin "2") (pinfunction "2_2") (pintype "input"))
      (node (ref "U23") (pin "3") (pinfunction "EN_3") (pintype "unspecified"))
    )
    (net (code "55") (name "RTS") (class "Default")
      (node (ref "Q2") (pin "3") (pinfunction "C_3") (pintype "input"))
      (node (ref "R7") (pin "1") (pinfunction "1_1") (pintype "input"))
      (node (ref "U7") (pin "19") (pinfunction "RTS_19") (pintype "unspecified"))
    )
    (net (code "56") (name "RXD") (class "Default")
      (node (ref "U23") (pin "34") (pinfunction "RXD0_34") (pintype "unspecified"))
      (node (ref "U7") (pin "21") (pinfunction "TXD_21") (pintype "unspecified"))
    )
    (net (code "57") (name "STAT") (class "Default")
      (node (ref "U23") (pin "13") (pinfunction "IO14_13") (pintype "unspecified"))
      (node (ref "U26") (pin "4") (pinfunction "STAT_4") (pintype "unspecified"))
    )
    (net (code "58") (name "TXD") (class "Default")
      (node (ref "U23") (pin "35") (pinfunction "TXD0_35") (pintype "unspecified"))
      (node (ref "U7") (pin "20") (pinfunction "RXD_20") (pintype "unspecified"))
    )
    (net (code "59") (name "VBUS") (class "Default")
      (node (ref "C5") (pin "2") (pinfunction "2_2") (pintype "input"))
      (node (ref "C7") (pin "2") (pinfunction "2_2") (pintype "input"))
      (node (ref "D1") (pin "2") (pinfunction "A_2") (pintype "input"))
      (node (ref "U7") (pin "8") (pinfunction "VBUS_8") (pintype "unspecified"))
      (node (ref "USB1") (pin "1") (pinfunction "VBUS_1") (pintype "unspecified"))
    )
    (net (code "60") (name "unconnected-(FPC3-Pad5)") (class "Default")
      (node (ref "FPC3") (pin "5") (pinfunction "5_5") (pintype "unspecified"))
    )
    (net (code "61") (name "unconnected-(FPC3-Pad6)") (class "Default")
      (node (ref "FPC3") (pin "6") (pinfunction "6_6") (pintype "unspecified"))
    )
    (net (code "62") (name "unconnected-(LED8-DO-Pad1)") (class "Default")
      (node (ref "LED8") (pin "1") (pinfunction "DO_1") (pintype "unspecified"))
    )
    (net (code "63") (name "unconnected-(U7-CTS-Pad18)") (class "Default")
      (node (ref "U7") (pin "18") (pinfunction "CTS_18") (pintype "unspecified"))
    )
    (net (code "64") (name "unconnected-(U7-DCD-Pad24)") (class "Default")
      (node (ref "U7") (pin "24") (pinfunction "DCD_24") (pintype "unspecified"))
    )
    (net (code "65") (name "unconnected-(U7-DSR-Pad22)") (class "Default")
      (node (ref "U7") (pin "22") (pinfunction "DSR_22") (pintype "unspecified"))
    )
    (net (code "66") (name "unconnected-(U7-GPIO.0-Pad14)") (class "Default")
      (node (ref "U7") (pin "14") (pinfunction "GPIO.0_14") (pintype "unspecified"))
    )
    (net (code "67") (name "unconnected-(U7-GPIO.1-Pad13)") (class "Default")
      (node (ref "U7") (pin "13") (pinfunction "GPIO.1_13") (pintype "unspecified"))
    )
    (net (code "68") (name "unconnected-(U7-GPIO.2-Pad12)") (class "Default")
      (node (ref "U7") (pin "12") (pinfunction "GPIO.2_12") (pintype "unspecified"))
    )
    (net (code "69") (name "unconnected-(U7-GPIO.3-Pad11)") (class "Default")
      (node (ref "U7") (pin "11") (pinfunction "GPIO.3_11") (pintype "unspecified"))
    )
    (net (code "70") (name "unconnected-(U7-NC-Pad10)") (class "Default")
      (node (ref "U7") (pin "10") (pinfunction "NC_10") (pintype "unspecified"))
    )
    (net (code "71") (name "unconnected-(U7-RI-Pad1)") (class "Default")
      (node (ref "U7") (pin "1") (pinfunction "RI_1") (pintype "unspecified"))
    )
    (net (code "72") (name "unconnected-(U7-RST#-Pad9)") (class "Default")
      (node (ref "U7") (pin "9") (pinfunction "RST#_9") (pintype "unspecified"))
    )
    (net (code "73") (name "unconnected-(U7-SUSPEND#-Pad15)") (class "Default")
      (node (ref "U7") (pin "15") (pinfunction "SUSPEND#_15") (pintype "unspecified"))
    )
    (net (code "74") (name "unconnected-(U7-SUSPEND-Pad17)") (class "Default")
      (node (ref "U7") (pin "17") (pinfunction "SUSPEND_17") (pintype "unspecified"))
    )
    (net (code "75") (name "unconnected-(U12-IO0-Pad15)") (class "Default")
      (node (ref "U12") (pin "15") (pinfunction "IO0_15") (pintype "unspecified"))
    )
    (net (code "76") (name "unconnected-(U12-IO1-Pad14)") (class "Default")
      (node (ref "U12") (pin "14") (pinfunction "IO1_14") (pintype "unspecified"))
    )
    (net (code "77") (name "unconnected-(U12-IO2-Pad13)") (class "Default")
      (node (ref "U12") (pin "13") (pinfunction "IO2_13") (pintype "unspecified"))
    )
    (net (code "78") (name "unconnected-(U12-IO3-Pad12)") (class "Default")
      (node (ref "U12") (pin "12") (pinfunction "IO3_12") (pintype "unspecified"))
    )
    (net (code "79") (name "unconnected-(U12-IO4-Pad11)") (class "Default")
      (node (ref "U12") (pin "11") (pinfunction "IO4_11") (pintype "unspecified"))
    )
    (net (code "80") (name "unconnected-(U12-IO5-Pad10)") (class "Default")
      (node (ref "U12") (pin "10") (pinfunction "IO5_10") (pintype "unspecified"))
    )
    (net (code "81") (name "unconnected-(U12-IO6-Pad9)") (class "Default")
      (node (ref "U12") (pin "9") (pinfunction "IO6_9") (pintype "unspecified"))
    )
    (net (code "82") (name "unconnected-(U12-IO7-Pad4)") (class "Default")
      (node (ref "U12") (pin "4") (pinfunction "IO7_4") (pintype "unspecified"))
    )
    (net (code "83") (name "unconnected-(U12-NC-Pad21)") (class "Default")
      (node (ref "U12") (pin "21") (pinfunction "NC_21") (pintype "unspecified"))
    )
    (net (code "84") (name "unconnected-(U12-NC-Pad23)") (class "Default")
      (node (ref "U12") (pin "23") (pinfunction "NC_23") (pintype "unspecified"))
    )
    (net (code "85") (name "unconnected-(U23-IO2-Pad24)") (class "Default")
      (node (ref "U23") (pin "24") (pinfunction "IO2_24") (pintype "unspecified"))
    )
    (net (code "86") (name "unconnected-(U23-IO12-Pad14)") (class "Default")
      (node (ref "U23") (pin "14") (pinfunction "IO12_14") (pintype "unspecified"))
    )
    (net (code "87") (name "unconnected-(U23-IO13-Pad16)") (class "Default")
      (node (ref "U23") (pin "16") (pinfunction "IO13_16") (pintype "unspecified"))
    )
    (net (code "88") (name "unconnected-(U23-IO15-Pad23)") (class "Default")
      (node (ref "U23") (pin "23") (pinfunction "IO15_23") (pintype "unspecified"))
    )
    (net (code "89") (name "unconnected-(U23-IO16-Pad27)") (class "Default")
      (node (ref "U23") (pin "27") (pinfunction "IO16_27") (pintype "unspecified"))
    )
    (net (code "90") (name "unconnected-(U23-IO17-Pad28)") (class "Default")
      (node (ref "U23") (pin "28") (pinfunction "IO17_28") (pintype "unspecified"))
    )
    (net (code "91") (name "unconnected-(U23-IO21-Pad33)") (class "Default")
      (node (ref "U23") (pin "33") (pinfunction "IO21_33") (pintype "unspecified"))
    )
    (net (code "92") (name "unconnected-(U23-IO22-Pad36)") (class "Default")
      (node (ref "U23") (pin "36") (pinfunction "IO22_36") (pintype "unspecified"))
    )
    (net (code "93") (name "unconnected-(U23-IO26-Pad11)") (class "Default")
      (node (ref "U23") (pin "11") (pinfunction "IO26_11") (pintype "unspecified"))
    )
    (net (code "94") (name "unconnected-(U23-NC-Pad17)") (class "Default")
      (node (ref "U23") (pin "17") (pinfunction "NC_17") (pintype "unspecified"))
    )
    (net (code "95") (name "unconnected-(U23-NC-Pad18)") (class "Default")
      (node (ref "U23") (pin "18") (pinfunction "NC_18") (pintype "unspecified"))
    )
    (net (code "96") (name "unconnected-(U23-NC-Pad19)") (class "Default")
      (node (ref "U23") (pin "19") (pinfunction "NC_19") (pintype "unspecified"))
    )
    (net (code "97") (name "unconnected-(U23-NC-Pad20)") (class "Default")
      (node (ref "U23") (pin "20") (pinfunction "NC_20") (pintype "unspecified"))
    )
    (net (code "98") (name "unconnected-(U23-NC-Pad21)") (class "Default")
      (node (ref "U23") (pin "21") (pinfunction "NC_21") (pintype "unspecified"))
    )
    (net (code "99") (name "unconnected-(U23-NC-Pad22)") (class "Default")
      (node (ref "U23") (pin "22") (pinfunction "NC_22") (pintype "unspecified"))
    )
    (net (code "100") (name "unconnected-(U23-NC-Pad32)") (class "Default")
      (node (ref "U23") (pin "32") (pinfunction "NC_32") (pintype "unspecified"))
    )
    (net (code "101") (name "unconnected-(U24-#OUT-Pad4)") (class "Default")
      (node (ref "U24") (pin "4") (pinfunction "#OUT_4") (pintype "unspecified"))
    )
    (net (code "102") (name "unconnected-(U24-CLEAR-Pad3)") (class "Default")
      (node (ref "U24") (pin "3") (pinfunction "CLEAR_3") (pintype "unspecified"))
    )
    (net (code "103") (name "unconnected-(U26-INT#-Pad7)") (class "Default")
      (node (ref "U26") (pin "7") (pinfunction "INT#_7") (pintype "unspecified"))
    )
    (net (code "104") (name "unconnected-(U26-NC-Pad8)") (class "Default")
      (node (ref "U26") (pin "8") (pinfunction "NC_8") (pintype "unspecified"))
    )
    (net (code "105") (name "unconnected-(U26-PMID_GOOD-Pad3)") (class "Default")
      (node (ref "U26") (pin "3") (pinfunction "PMID_GOOD_3") (pintype "unspecified"))
    )
    (net (code "106") (name "unconnected-(U26-PSEL-Pad2)") (class "Default")
      (node (ref "U26") (pin "2") (pinfunction "PSEL_2") (pintype "unspecified"))
    )
    (net (code "107") (name "unconnected-(U26-QON#-Pad12)") (class "Default")
      (node (ref "U26") (pin "12") (pinfunction "QON#_12") (pintype "unspecified"))
    )
    (net (code "108") (name "unconnected-(U26-SCL-Pad5)") (class "Default")
      (node (ref "U26") (pin "5") (pinfunction "SCL_5") (pintype "unspecified"))
    )
    (net (code "109") (name "unconnected-(U26-SDA-Pad6)") (class "Default")
      (node (ref "U26") (pin "6") (pinfunction "SDA_6") (pintype "unspecified"))
    )
    (net (code "110") (name "unconnected-(USB1-ID-Pad4)") (class "Default")
      (node (ref "USB1") (pin "4") (pinfunction "ID_4") (pintype "unspecified"))
    )
  )
)
